# PSoC4_Prototyping_Kit_DCO.net
KiCad netlist of a schematic drawn in EAGLE
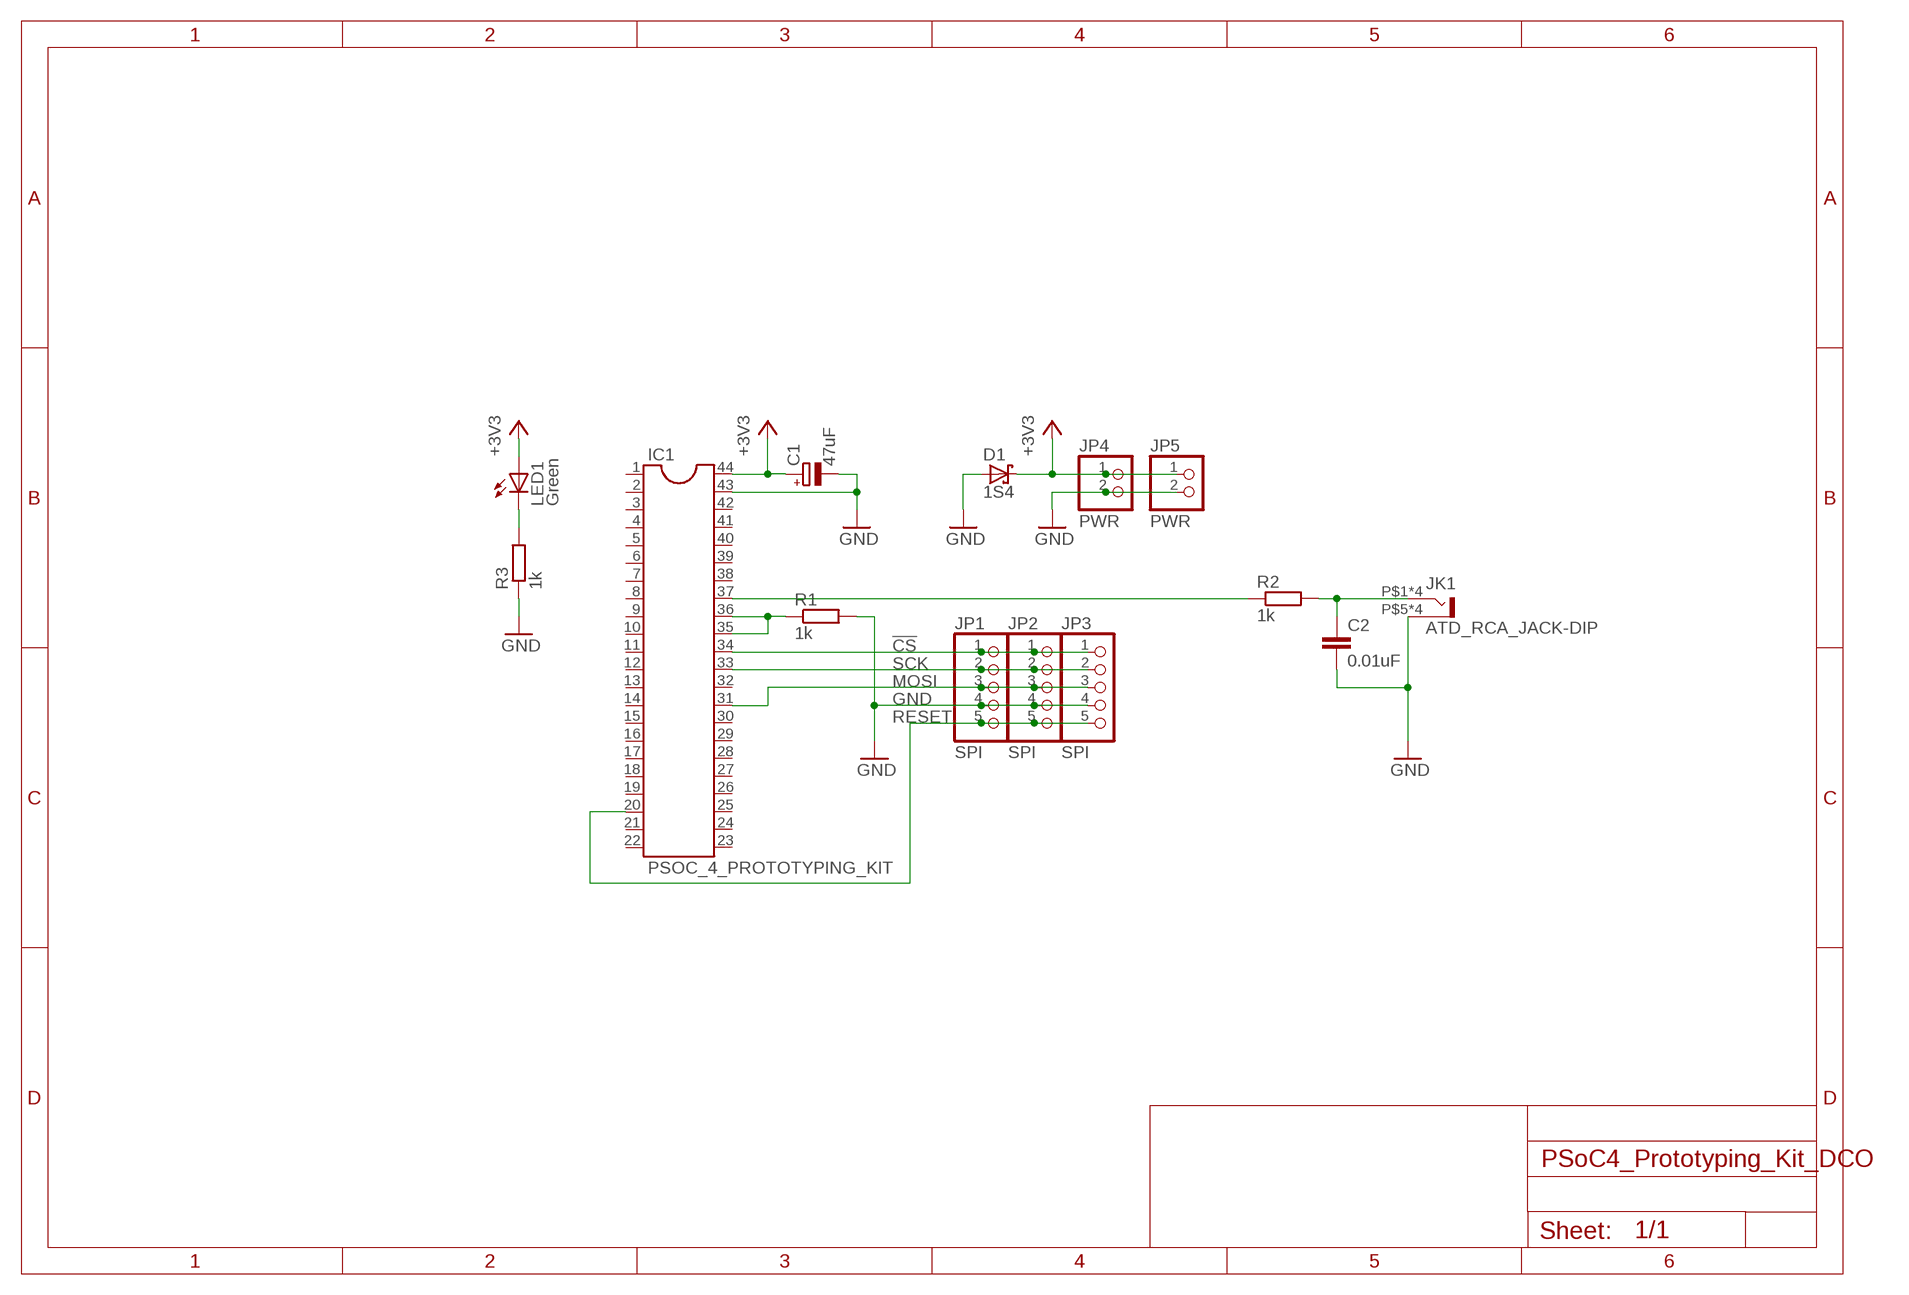
[diagram p0: schematic, sheet 1]

(export (version "E")
  (design (tool "Eeschema 10.0.6"))
  (components
    (comp (ref "C1")
      (value "47uF")
      (footprint "eagle-import:E2,5-5")
      (libsource (lib "eagle-import") (part "CPOL-EUE2.5-5"))
    )
    (comp (ref "C2")
      (value "0.01uF")
      (footprint "eagle-import:C050-024X044")
      (libsource (lib "eagle-import") (part "C-EU050-024X044"))
    )
    (comp (ref "D1")
      (value "1S4")
      (footprint "eagle-import:DO35-7")
      (libsource (lib "eagle-import") (part "SCHOTTKY-DIODEDO35-7"))
    )
    (comp (ref "IC1")
      (value "PSOC_4_PROTOTYPING_KIT")
      (footprint "eagle-import:DIL44-8")
      (libsource (lib "eagle-import") (part "PSOC_PROTOTYPING_KIT"))
    )
    (comp (ref "JK1")
      (value "ATD_RCA_JACK-DIP")
      (footprint "eagle-import:ATD_RCA_JACK_DIP")
      (libsource (lib "eagle-import") (part "ATD_RCA_JACK-DIP"))
    )
    (comp (ref "JP1")
      (value "SPI")
      (footprint "eagle-import:1X05")
      (libsource (lib "eagle-import") (part "PINHD-1X5"))
    )
    (comp (ref "JP2")
      (value "SPI")
      (footprint "eagle-import:1X05")
      (libsource (lib "eagle-import") (part "PINHD-1X5"))
    )
    (comp (ref "JP3")
      (value "SPI")
      (footprint "eagle-import:1X05")
      (libsource (lib "eagle-import") (part "PINHD-1X5"))
    )
    (comp (ref "JP4")
      (value "PWR")
      (footprint "eagle-import:1X02")
      (libsource (lib "eagle-import") (part "PINHD-1X2"))
    )
    (comp (ref "JP5")
      (value "PWR")
      (footprint "eagle-import:1X02")
      (libsource (lib "eagle-import") (part "PINHD-1X2"))
    )
    (comp (ref "LED1")
      (value "Green")
      (footprint "eagle-import:LED3MM")
      (libsource (lib "eagle-import") (part "LED3MM"))
    )
    (comp (ref "R1")
      (value "1k")
      (footprint "eagle-import:0207_7")
      (libsource (lib "eagle-import") (part "R-EU_0207/7"))
    )
    (comp (ref "R2")
      (value "1k")
      (footprint "eagle-import:0207_7")
      (libsource (lib "eagle-import") (part "R-EU_0207/7"))
    )
    (comp (ref "R3")
      (value "1k")
      (footprint "eagle-import:0207_7")
      (libsource (lib "eagle-import") (part "R-EU_0207/7"))
    )
  )
  (nets
    (net (code "1") (name "+3V3") (class "Default")
      (node (ref "C1") (pin "+") (pinfunction "+_+") (pintype "passive"))
      (node (ref "D1") (pin "C") (pinfunction "C_C") (pintype "passive"))
      (node (ref "IC1") (pin "44") (pinfunction "44_44") (pintype "passive"))
      (node (ref "JP4") (pin "1") (pinfunction "1_1") (pintype "passive"))
      (node (ref "JP5") (pin "1") (pinfunction "1_1") (pintype "passive"))
      (node (ref "LED1") (pin "A") (pinfunction "A_A") (pintype "passive"))
    )
    (net (code "2") (name "/MOSI") (class "Default")
      (node (ref "IC1") (pin "31") (pinfunction "31_31") (pintype "passive"))
      (node (ref "JP1") (pin "3") (pinfunction "3_3") (pintype "passive"))
      (node (ref "JP2") (pin "3") (pinfunction "3_3") (pintype "passive"))
      (node (ref "JP3") (pin "3") (pinfunction "3_3") (pintype "passive"))
    )
    (net (code "3") (name "/RESET") (class "Default")
      (node (ref "IC1") (pin "20") (pinfunction "20_20") (pintype "passive"))
      (node (ref "JP1") (pin "5") (pinfunction "5_5") (pintype "passive"))
      (node (ref "JP2") (pin "5") (pinfunction "5_5") (pintype "passive"))
      (node (ref "JP3") (pin "5") (pinfunction "5_5") (pintype "passive"))
    )
    (net (code "4") (name "/SCK") (class "Default")
      (node (ref "IC1") (pin "33") (pinfunction "33_33") (pintype "passive"))
      (node (ref "JP1") (pin "2") (pinfunction "2_2") (pintype "passive"))
      (node (ref "JP2") (pin "2") (pinfunction "2_2") (pintype "passive"))
      (node (ref "JP3") (pin "2") (pinfunction "2_2") (pintype "passive"))
    )
    (net (code "5") (name "/~{CS}") (class "Default")
      (node (ref "IC1") (pin "34") (pinfunction "34_34") (pintype "passive"))
      (node (ref "JP1") (pin "1") (pinfunction "1_1") (pintype "passive"))
      (node (ref "JP2") (pin "1") (pinfunction "1_1") (pintype "passive"))
      (node (ref "JP3") (pin "1") (pinfunction "1_1") (pintype "passive"))
    )
    (net (code "6") (name "GND") (class "Default")
      (node (ref "C1") (pin "-") (pinfunction "-_-") (pintype "passive"))
      (node (ref "C2") (pin "2") (pinfunction "2_2") (pintype "passive"))
      (node (ref "D1") (pin "A") (pinfunction "A_A") (pintype "passive"))
      (node (ref "IC1") (pin "43") (pinfunction "43_43") (pintype "passive"))
      (node (ref "JK1") (pin "P$5") (pinfunction "S_P$5") (pintype "passive"))
      (node (ref "JK1") (pin "P$6") (pinfunction "S_P$6") (pintype "passive"))
      (node (ref "JK1") (pin "P$7") (pinfunction "S_P$7") (pintype "passive"))
      (node (ref "JK1") (pin "P$8") (pinfunction "S_P$8") (pintype "passive"))
      (node (ref "JP1") (pin "4") (pinfunction "4_4") (pintype "passive"))
      (node (ref "JP2") (pin "4") (pinfunction "4_4") (pintype "passive"))
      (node (ref "JP3") (pin "4") (pinfunction "4_4") (pintype "passive"))
      (node (ref "JP4") (pin "2") (pinfunction "2_2") (pintype "passive"))
      (node (ref "JP5") (pin "2") (pinfunction "2_2") (pintype "passive"))
      (node (ref "R1") (pin "2") (pinfunction "2_2") (pintype "passive"))
      (node (ref "R3") (pin "1") (pinfunction "1_1") (pintype "passive"))
    )
    (net (code "7") (name "Net-(C2-Pad1)") (class "Default")
      (node (ref "C2") (pin "1") (pinfunction "1_1") (pintype "passive"))
      (node (ref "JK1") (pin "P$1") (pinfunction "T_P$1") (pintype "passive"))
      (node (ref "JK1") (pin "P$2") (pinfunction "T_P$2") (pintype "passive"))
      (node (ref "JK1") (pin "P$3") (pinfunction "T_P$3") (pintype "passive"))
      (node (ref "JK1") (pin "P$4") (pinfunction "T_P$4") (pintype "passive"))
      (node (ref "R2") (pin "2") (pinfunction "2_2") (pintype "passive"))
    )
    (net (code "8") (name "Net-(IC1-Pad35)") (class "Default")
      (node (ref "IC1") (pin "35") (pinfunction "35_35") (pintype "passive"))
      (node (ref "IC1") (pin "36") (pinfunction "36_36") (pintype "passive"))
      (node (ref "R1") (pin "1") (pinfunction "1_1") (pintype "passive"))
    )
    (net (code "9") (name "Net-(IC1-Pad37)") (class "Default")
      (node (ref "IC1") (pin "37") (pinfunction "37_37") (pintype "passive"))
      (node (ref "R2") (pin "1") (pinfunction "1_1") (pintype "passive"))
    )
    (net (code "10") (name "Net-(LED1-C)") (class "Default")
      (node (ref "LED1") (pin "K") (pinfunction "C_K") (pintype "passive"))
      (node (ref "R3") (pin "2") (pinfunction "2_2") (pintype "passive"))
    )
    (net (code "11") (name "unconnected-(IC1-Pad1)") (class "Default")
      (node (ref "IC1") (pin "1") (pinfunction "1_1") (pintype "passive"))
    )
    (net (code "12") (name "unconnected-(IC1-Pad2)") (class "Default")
      (node (ref "IC1") (pin "2") (pinfunction "2_2") (pintype "passive"))
    )
    (net (code "13") (name "unconnected-(IC1-Pad3)") (class "Default")
      (node (ref "IC1") (pin "3") (pinfunction "3_3") (pintype "passive"))
    )
    (net (code "14") (name "unconnected-(IC1-Pad4)") (class "Default")
      (node (ref "IC1") (pin "4") (pinfunction "4_4") (pintype "passive"))
    )
    (net (code "15") (name "unconnected-(IC1-Pad5)") (class "Default")
      (node (ref "IC1") (pin "5") (pinfunction "5_5") (pintype "passive"))
    )
    (net (code "16") (name "unconnected-(IC1-Pad6)") (class "Default")
      (node (ref "IC1") (pin "6") (pinfunction "6_6") (pintype "passive"))
    )
    (net (code "17") (name "unconnected-(IC1-Pad7)") (class "Default")
      (node (ref "IC1") (pin "7") (pinfunction "7_7") (pintype "passive"))
    )
    (net (code "18") (name "unconnected-(IC1-Pad8)") (class "Default")
      (node (ref "IC1") (pin "8") (pinfunction "8_8") (pintype "passive"))
    )
    (net (code "19") (name "unconnected-(IC1-Pad9)") (class "Default")
      (node (ref "IC1") (pin "9") (pinfunction "9_9") (pintype "passive"))
    )
    (net (code "20") (name "unconnected-(IC1-Pad10)") (class "Default")
      (node (ref "IC1") (pin "10") (pinfunction "10_10") (pintype "passive"))
    )
    (net (code "21") (name "unconnected-(IC1-Pad11)") (class "Default")
      (node (ref "IC1") (pin "11") (pinfunction "11_11") (pintype "passive"))
    )
    (net (code "22") (name "unconnected-(IC1-Pad12)") (class "Default")
      (node (ref "IC1") (pin "12") (pinfunction "12_12") (pintype "passive"))
    )
    (net (code "23") (name "unconnected-(IC1-Pad13)") (class "Default")
      (node (ref "IC1") (pin "13") (pinfunction "13_13") (pintype "passive"))
    )
    (net (code "24") (name "unconnected-(IC1-Pad14)") (class "Default")
      (node (ref "IC1") (pin "14") (pinfunction "14_14") (pintype "passive"))
    )
    (net (code "25") (name "unconnected-(IC1-Pad15)") (class "Default")
      (node (ref "IC1") (pin "15") (pinfunction "15_15") (pintype "passive"))
    )
    (net (code "26") (name "unconnected-(IC1-Pad16)") (class "Default")
      (node (ref "IC1") (pin "16") (pinfunction "16_16") (pintype "passive"))
    )
    (net (code "27") (name "unconnected-(IC1-Pad17)") (class "Default")
      (node (ref "IC1") (pin "17") (pinfunction "17_17") (pintype "passive"))
    )
    (net (code "28") (name "unconnected-(IC1-Pad18)") (class "Default")
      (node (ref "IC1") (pin "18") (pinfunction "18_18") (pintype "passive"))
    )
    (net (code "29") (name "unconnected-(IC1-Pad19)") (class "Default")
      (node (ref "IC1") (pin "19") (pinfunction "19_19") (pintype "passive"))
    )
    (net (code "30") (name "unconnected-(IC1-Pad21)") (class "Default")
      (node (ref "IC1") (pin "21") (pinfunction "21_21") (pintype "passive"))
    )
    (net (code "31") (name "unconnected-(IC1-Pad22)") (class "Default")
      (node (ref "IC1") (pin "22") (pinfunction "22_22") (pintype "passive"))
    )
    (net (code "32") (name "unconnected-(IC1-Pad23)") (class "Default")
      (node (ref "IC1") (pin "23") (pinfunction "23_23") (pintype "passive"))
    )
    (net (code "33") (name "unconnected-(IC1-Pad24)") (class "Default")
      (node (ref "IC1") (pin "24") (pinfunction "24_24") (pintype "passive"))
    )
    (net (code "34") (name "unconnected-(IC1-Pad25)") (class "Default")
      (node (ref "IC1") (pin "25") (pinfunction "25_25") (pintype "passive"))
    )
    (net (code "35") (name "unconnected-(IC1-Pad26)") (class "Default")
      (node (ref "IC1") (pin "26") (pinfunction "26_26") (pintype "passive"))
    )
    (net (code "36") (name "unconnected-(IC1-Pad27)") (class "Default")
      (node (ref "IC1") (pin "27") (pinfunction "27_27") (pintype "passive"))
    )
    (net (code "37") (name "unconnected-(IC1-Pad28)") (class "Default")
      (node (ref "IC1") (pin "28") (pinfunction "28_28") (pintype "passive"))
    )
    (net (code "38") (name "unconnected-(IC1-Pad29)") (class "Default")
      (node (ref "IC1") (pin "29") (pinfunction "29_29") (pintype "passive"))
    )
    (net (code "39") (name "unconnected-(IC1-Pad30)") (class "Default")
      (node (ref "IC1") (pin "30") (pinfunction "30_30") (pintype "passive"))
    )
    (net (code "40") (name "unconnected-(IC1-Pad32)") (class "Default")
      (node (ref "IC1") (pin "32") (pinfunction "32_32") (pintype "passive"))
    )
    (net (code "41") (name "unconnected-(IC1-Pad38)") (class "Default")
      (node (ref "IC1") (pin "38") (pinfunction "38_38") (pintype "passive"))
    )
    (net (code "42") (name "unconnected-(IC1-Pad39)") (class "Default")
      (node (ref "IC1") (pin "39") (pinfunction "39_39") (pintype "passive"))
    )
    (net (code "43") (name "unconnected-(IC1-Pad40)") (class "Default")
      (node (ref "IC1") (pin "40") (pinfunction "40_40") (pintype "passive"))
    )
    (net (code "44") (name "unconnected-(IC1-Pad41)") (class "Default")
      (node (ref "IC1") (pin "41") (pinfunction "41_41") (pintype "passive"))
    )
    (net (code "45") (name "unconnected-(IC1-Pad42)") (class "Default")
      (node (ref "IC1") (pin "42") (pinfunction "42_42") (pintype "passive"))
    )
  )
)
